# working.net
KiCad netlist of a schematic drawn in EAGLE
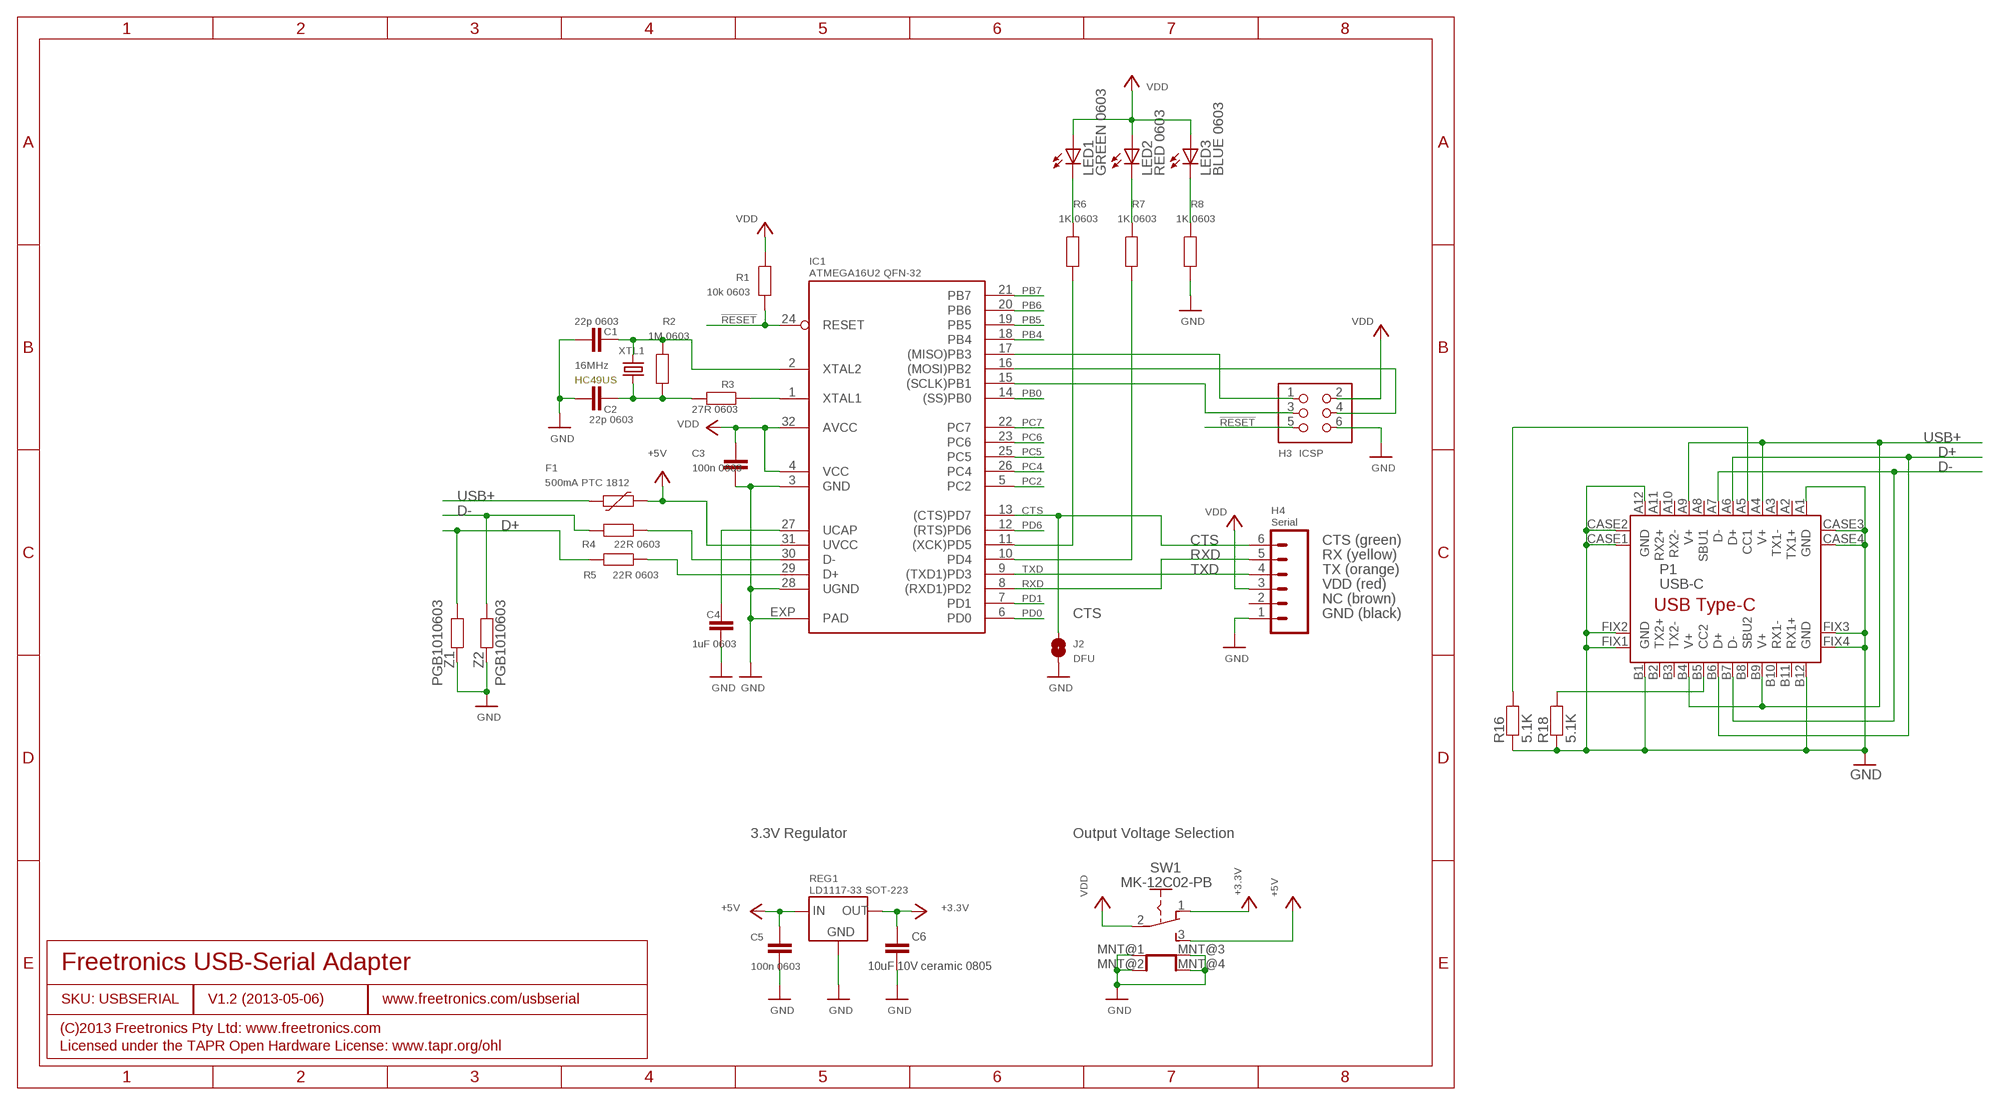
[diagram p0: schematic, sheet 1]

(export (version "E")
  (design (tool "Eeschema 10.0.6"))
  (components
    (comp (ref "C1")
      (value "22p 0603")
      (footprint "eagle-import:0603")
      (libsource (lib "eagle-import") (part "CAP0603"))
    )
    (comp (ref "C2")
      (value "22p 0603")
      (footprint "eagle-import:0603")
      (libsource (lib "eagle-import") (part "CAP0603"))
    )
    (comp (ref "C3")
      (value "100n 0603")
      (footprint "eagle-import:0603")
      (libsource (lib "eagle-import") (part "CAP0603"))
    )
    (comp (ref "C4")
      (value "1uF 0603")
      (footprint "eagle-import:0603")
      (libsource (lib "eagle-import") (part "CAP0603"))
    )
    (comp (ref "C5")
      (value "100n 0603")
      (footprint "eagle-import:0603")
      (libsource (lib "eagle-import") (part "CAP0603"))
    )
    (comp (ref "C6")
      (value "10uF 10V ceramic 0805")
      (footprint "eagle-import:C0805")
      (libsource (lib "eagle-import") (part "C-EUC0805"))
    )
    (comp (ref "F1")
      (value "500mA PTC 1812")
      (footprint "eagle-import:1812")
      (libsource (lib "eagle-import") (part "PTC"))
    )
    (comp (ref "H3")
      (value "ICSP")
      (footprint "eagle-import:HEADER_2X3")
      (libsource (lib "eagle-import") (part "HEADER_2X3"))
    )
    (comp (ref "H4")
      (value "Serial")
      (footprint "eagle-import:1X06")
      (libsource (lib "eagle-import") (part "M06SIP"))
    )
    (comp (ref "IC1")
      (value "ATMEGA16U2 QFN-32")
      (footprint "eagle-import:ATMEL_QFN32")
      (libsource (lib "eagle-import") (part "ATMEL_ATMEGA8U2-MUQFN"))
    )
    (comp (ref "J2") (value "DFU") (footprint "eagle-import:SJ") (libsource (lib "eagle-import") (part "SJ")))
    (comp (ref "LED1")
      (value "GREEN 0603")
      (footprint "eagle-import:LED-0603")
      (libsource (lib "eagle-import") (part "LED0603"))
    )
    (comp (ref "LED2")
      (value "RED 0603")
      (footprint "eagle-import:LED-0603")
      (libsource (lib "eagle-import") (part "LED0603"))
    )
    (comp (ref "LED3")
      (value "BLUE 0603")
      (footprint "eagle-import:LED-0603")
      (libsource (lib "eagle-import") (part "LED0603"))
    )
    (comp (ref "P1")
      (value "USB-C")
      (footprint "eagle-import:USB-C-U52A")
      (libsource (lib "eagle-import") (part "USB-C"))
    )
    (comp (ref "R1")
      (value "10k 0603")
      (footprint "eagle-import:0603")
      (libsource (lib "eagle-import") (part "RESISTOR0603"))
    )
    (comp (ref "R2")
      (value "1M 0603")
      (footprint "eagle-import:0603")
      (libsource (lib "eagle-import") (part "RESISTOR0603"))
    )
    (comp (ref "R3")
      (value "27R 0603")
      (footprint "eagle-import:0603")
      (libsource (lib "eagle-import") (part "RESISTOR0603"))
    )
    (comp (ref "R4")
      (value "22R 0603")
      (footprint "eagle-import:0603")
      (libsource (lib "eagle-import") (part "RESISTOR0603"))
    )
    (comp (ref "R5")
      (value "22R 0603")
      (footprint "eagle-import:0603")
      (libsource (lib "eagle-import") (part "RESISTOR0603"))
    )
    (comp (ref "R6")
      (value "1K 0603")
      (footprint "eagle-import:0603")
      (libsource (lib "eagle-import") (part "RESISTOR0603"))
    )
    (comp (ref "R7")
      (value "1K 0603")
      (footprint "eagle-import:0603")
      (libsource (lib "eagle-import") (part "RESISTOR0603"))
    )
    (comp (ref "R8")
      (value "1K 0603")
      (footprint "eagle-import:0603")
      (libsource (lib "eagle-import") (part "RESISTOR0603"))
    )
    (comp (ref "R16")
      (value "5.1K")
      (footprint "eagle-import:0603")
      (libsource (lib "eagle-import") (part "freetronics-original_RESISTOR0603"))
    )
    (comp (ref "R18")
      (value "5.1K")
      (footprint "eagle-import:0603")
      (libsource (lib "eagle-import") (part "freetronics-original_RESISTOR0603"))
    )
    (comp (ref "REG1")
      (value "LD1117-33 SOT-223")
      (footprint "eagle-import:SOT-223")
      (libsource (lib "eagle-import") (part "LD1117-FIXED"))
    )
    (comp (ref "SW1")
      (value "MK-12C02-PB")
      (footprint "eagle-import:MK-12C02")
      (libsource (lib "eagle-import") (part "SWITCH-SPDT-4TABSSMT"))
    )
    (comp (ref "XTL1")
      (value "16MHz")
      (footprint "eagle-import:HC49U-V")
      (libsource (lib "eagle-import") (part "CRYSTALHC49UV"))
    )
    (comp (ref "Z1")
      (value "PGB1010603")
      (footprint "eagle-import:0603")
      (libsource (lib "eagle-import") (part "RESISTOR0603"))
    )
    (comp (ref "Z2")
      (value "PGB1010603")
      (footprint "eagle-import:0603")
      (libsource (lib "eagle-import") (part "RESISTOR0603"))
    )
  )
  (nets
    (net (code "1") (name "+3.3V") (class "Default")
      (node (ref "C6") (pin "1") (pinfunction "1_1") (pintype "passive"))
      (node (ref "REG1") (pin "2") (pinfunction "OUT_2") (pintype "power_in"))
      (node (ref "REG1") (pin "4") (pinfunction "OUT_4") (pintype "power_in"))
      (node (ref "SW1") (pin "1") (pinfunction "A_1") (pintype "passive"))
    )
    (net (code "2") (name "+5V") (class "Default")
      (node (ref "C5") (pin "1") (pinfunction "1_1") (pintype "passive"))
      (node (ref "F1") (pin "2") (pinfunction "P$2_2") (pintype "bidirectional"))
      (node (ref "IC1") (pin "31") (pinfunction "UVCC_31") (pintype "power_in"))
      (node (ref "REG1") (pin "3") (pinfunction "IN_3") (pintype "input"))
      (node (ref "SW1") (pin "3") (pinfunction "B_3") (pintype "passive"))
    )
    (net (code "3") (name "/CTS") (class "Default")
      (node (ref "H4") (pin "6") (pinfunction "6_6") (pintype "passive"))
      (node (ref "IC1") (pin "13") (pinfunction "(CTS)PD7_13") (pintype "bidirectional"))
      (node (ref "J2") (pin "2") (pinfunction "2_2") (pintype "passive"))
    )
    (net (code "4") (name "/D+") (class "Default")
      (node (ref "P1") (pin "A6") (pinfunction "D+_A6") (pintype "bidirectional"))
      (node (ref "P1") (pin "B6") (pinfunction "D+_B6") (pintype "bidirectional"))
      (node (ref "R5") (pin "2") (pinfunction "2_2") (pintype "passive"))
      (node (ref "Z1") (pin "1") (pinfunction "1_1") (pintype "passive"))
    )
    (net (code "5") (name "/D-") (class "Default")
      (node (ref "P1") (pin "A7") (pinfunction "D-_A7") (pintype "bidirectional"))
      (node (ref "P1") (pin "B7") (pinfunction "D-_B7") (pintype "bidirectional"))
      (node (ref "R4") (pin "2") (pinfunction "2_2") (pintype "passive"))
      (node (ref "Z2") (pin "1") (pinfunction "1_1") (pintype "passive"))
    )
    (net (code "6") (name "/PB0") (class "Default")
      (node (ref "IC1") (pin "14") (pinfunction "(SS)PB0_14") (pintype "bidirectional"))
    )
    (net (code "7") (name "/PB4") (class "Default")
      (node (ref "IC1") (pin "18") (pinfunction "PB4_18") (pintype "bidirectional"))
    )
    (net (code "8") (name "/PB5") (class "Default")
      (node (ref "IC1") (pin "19") (pinfunction "PB5_19") (pintype "bidirectional"))
    )
    (net (code "9") (name "/PB6") (class "Default")
      (node (ref "IC1") (pin "20") (pinfunction "PB6_20") (pintype "bidirectional"))
    )
    (net (code "10") (name "/PB7") (class "Default")
      (node (ref "IC1") (pin "21") (pinfunction "PB7_21") (pintype "bidirectional"))
    )
    (net (code "11") (name "/PC2") (class "Default")
      (node (ref "IC1") (pin "5") (pinfunction "PC2_5") (pintype "bidirectional"))
    )
    (net (code "12") (name "/PC4") (class "Default")
      (node (ref "IC1") (pin "26") (pinfunction "PC4_26") (pintype "bidirectional"))
    )
    (net (code "13") (name "/PC5") (class "Default")
      (node (ref "IC1") (pin "25") (pinfunction "PC5_25") (pintype "bidirectional"))
    )
    (net (code "14") (name "/PC6") (class "Default")
      (node (ref "IC1") (pin "23") (pinfunction "PC6_23") (pintype "bidirectional"))
    )
    (net (code "15") (name "/PC7") (class "Default")
      (node (ref "IC1") (pin "22") (pinfunction "PC7_22") (pintype "bidirectional"))
    )
    (net (code "16") (name "/PD0") (class "Default")
      (node (ref "IC1") (pin "6") (pinfunction "PD0_6") (pintype "bidirectional"))
    )
    (net (code "17") (name "/PD1") (class "Default")
      (node (ref "IC1") (pin "7") (pinfunction "PD1_7") (pintype "bidirectional"))
    )
    (net (code "18") (name "/PD6") (class "Default")
      (node (ref "IC1") (pin "12") (pinfunction "(RTS)PD6_12") (pintype "bidirectional"))
    )
    (net (code "19") (name "/RXD") (class "Default")
      (node (ref "H4") (pin "5") (pinfunction "5_5") (pintype "passive"))
      (node (ref "IC1") (pin "8") (pinfunction "(RXD1)PD2_8") (pintype "bidirectional"))
    )
    (net (code "20") (name "/TXD") (class "Default")
      (node (ref "H4") (pin "4") (pinfunction "4_4") (pintype "passive"))
      (node (ref "IC1") (pin "9") (pinfunction "(TXD1)PD3_9") (pintype "bidirectional"))
    )
    (net (code "21") (name "/USB+") (class "Default")
      (node (ref "F1") (pin "1") (pinfunction "P$1_1") (pintype "bidirectional"))
      (node (ref "P1") (pin "A4") (pinfunction "V+_A4") (pintype "power_in"))
      (node (ref "P1") (pin "A9") (pinfunction "V+_A9") (pintype "power_in"))
      (node (ref "P1") (pin "B4") (pinfunction "V+_B4") (pintype "power_in"))
      (node (ref "P1") (pin "B9") (pinfunction "V+_B9") (pintype "power_in"))
    )
    (net (code "22") (name "/~{RESET}") (class "Default")
      (node (ref "H3") (pin "5") (pinfunction "5_5") (pintype "passive"))
      (node (ref "IC1") (pin "24") (pinfunction "RESET_24") (pintype "input"))
      (node (ref "R1") (pin "1") (pinfunction "1_1") (pintype "passive"))
    )
    (net (code "23") (name "GND") (class "Default")
      (node (ref "C1") (pin "1") (pinfunction "1_1") (pintype "passive"))
      (node (ref "C2") (pin "1") (pinfunction "1_1") (pintype "passive"))
      (node (ref "C3") (pin "2") (pinfunction "2_2") (pintype "passive"))
      (node (ref "C4") (pin "2") (pinfunction "2_2") (pintype "passive"))
      (node (ref "C5") (pin "2") (pinfunction "2_2") (pintype "passive"))
      (node (ref "C6") (pin "2") (pinfunction "2_2") (pintype "passive"))
      (node (ref "H3") (pin "6") (pinfunction "6_6") (pintype "passive"))
      (node (ref "H4") (pin "1") (pinfunction "1_1") (pintype "passive"))
      (node (ref "IC1") (pin "28") (pinfunction "UGND_28") (pintype "power_in"))
      (node (ref "IC1") (pin "3") (pinfunction "GND_3") (pintype "power_in"))
      (node (ref "IC1") (pin "EXP") (pinfunction "PAD_EXP") (pintype "power_in"))
      (node (ref "J2") (pin "1") (pinfunction "1_1") (pintype "passive"))
      (node (ref "P1") (pin "A1") (pinfunction "GND_A1") (pintype "power_in"))
      (node (ref "P1") (pin "A12") (pinfunction "GND_A12") (pintype "power_in"))
      (node (ref "P1") (pin "B1") (pinfunction "GND_B1") (pintype "power_in"))
      (node (ref "P1") (pin "B12") (pinfunction "GND_B12") (pintype "power_in"))
      (node (ref "P1") (pin "CASE1") (pinfunction "GND_CASE1") (pintype "power_in"))
      (node (ref "P1") (pin "CASE2") (pinfunction "GND_CASE2") (pintype "power_in"))
      (node (ref "P1") (pin "CASE3") (pinfunction "GND_CASE3") (pintype "power_in"))
      (node (ref "P1") (pin "CASE4") (pinfunction "GND_CASE4") (pintype "power_in"))
      (node (ref "P1") (pin "FIX1") (pinfunction "GND_FIX1") (pintype "power_in"))
      (node (ref "P1") (pin "FIX2") (pinfunction "GND_FIX2") (pintype "power_in"))
      (node (ref "P1") (pin "FIX3") (pinfunction "GND_FIX3") (pintype "power_in"))
      (node (ref "P1") (pin "FIX4") (pinfunction "GND_FIX4") (pintype "power_in"))
      (node (ref "R16") (pin "1") (pinfunction "1_1") (pintype "passive"))
      (node (ref "R18") (pin "1") (pinfunction "1_1") (pintype "passive"))
      (node (ref "R8") (pin "1") (pinfunction "1_1") (pintype "passive"))
      (node (ref "REG1") (pin "1") (pinfunction "GND_1") (pintype "input"))
      (node (ref "SW1") (pin "MNT@1") (pinfunction "MNT_MNT@1") (pintype "bidirectional"))
      (node (ref "SW1") (pin "MNT@2") (pinfunction "MNT_MNT@2") (pintype "bidirectional"))
      (node (ref "SW1") (pin "MNT@3") (pinfunction "MNT_MNT@3") (pintype "bidirectional"))
      (node (ref "SW1") (pin "MNT@4") (pinfunction "MNT_MNT@4") (pintype "bidirectional"))
      (node (ref "Z1") (pin "2") (pinfunction "2_2") (pintype "passive"))
      (node (ref "Z2") (pin "2") (pinfunction "2_2") (pintype "passive"))
    )
    (net (code "24") (name "Net-(C2-Pad2)") (class "Default")
      (node (ref "C2") (pin "2") (pinfunction "2_2") (pintype "passive"))
      (node (ref "R2") (pin "1") (pinfunction "1_1") (pintype "passive"))
      (node (ref "R3") (pin "2") (pinfunction "2_2") (pintype "passive"))
      (node (ref "XTL1") (pin "1") (pinfunction "1_1") (pintype "passive"))
    )
    (net (code "25") (name "Net-(IC1-(MISO)PB3)") (class "Default")
      (node (ref "H3") (pin "1") (pinfunction "1_1") (pintype "passive"))
      (node (ref "IC1") (pin "17") (pinfunction "(MISO)PB3_17") (pintype "bidirectional"))
    )
    (net (code "26") (name "Net-(IC1-(MOSI)PB2)") (class "Default")
      (node (ref "H3") (pin "4") (pinfunction "4_4") (pintype "passive"))
      (node (ref "IC1") (pin "16") (pinfunction "(MOSI)PB2_16") (pintype "bidirectional"))
    )
    (net (code "27") (name "Net-(IC1-(SCLK)PB1)") (class "Default")
      (node (ref "H3") (pin "3") (pinfunction "3_3") (pintype "passive"))
      (node (ref "IC1") (pin "15") (pinfunction "(SCLK)PB1_15") (pintype "bidirectional"))
    )
    (net (code "28") (name "Net-(IC1-(XCK)PD5)") (class "Default")
      (node (ref "IC1") (pin "11") (pinfunction "(XCK)PD5_11") (pintype "bidirectional"))
      (node (ref "R6") (pin "1") (pinfunction "1_1") (pintype "passive"))
    )
    (net (code "29") (name "Net-(IC1-D+)") (class "Default")
      (node (ref "IC1") (pin "29") (pinfunction "D+_29") (pintype "bidirectional"))
      (node (ref "R5") (pin "1") (pinfunction "1_1") (pintype "passive"))
    )
    (net (code "30") (name "Net-(IC1-D-)") (class "Default")
      (node (ref "IC1") (pin "30") (pinfunction "D-_30") (pintype "bidirectional"))
      (node (ref "R4") (pin "1") (pinfunction "1_1") (pintype "passive"))
    )
    (net (code "31") (name "Net-(IC1-PD4)") (class "Default")
      (node (ref "IC1") (pin "10") (pinfunction "PD4_10") (pintype "bidirectional"))
      (node (ref "R7") (pin "1") (pinfunction "1_1") (pintype "passive"))
    )
    (net (code "32") (name "Net-(IC1-UCAP)") (class "Default")
      (node (ref "C4") (pin "1") (pinfunction "1_1") (pintype "passive"))
      (node (ref "IC1") (pin "27") (pinfunction "UCAP_27") (pintype "passive"))
    )
    (net (code "33") (name "Net-(IC1-XTAL1)") (class "Default")
      (node (ref "IC1") (pin "1") (pinfunction "XTAL1_1") (pintype "bidirectional"))
      (node (ref "R3") (pin "1") (pinfunction "1_1") (pintype "passive"))
    )
    (net (code "34") (name "Net-(IC1-XTAL2)") (class "Default")
      (node (ref "C1") (pin "2") (pinfunction "2_2") (pintype "passive"))
      (node (ref "IC1") (pin "2") (pinfunction "XTAL2_2") (pintype "bidirectional"))
      (node (ref "R2") (pin "2") (pinfunction "2_2") (pintype "passive"))
      (node (ref "XTL1") (pin "2") (pinfunction "2_2") (pintype "passive"))
    )
    (net (code "35") (name "Net-(LED1-PadC)") (class "Default")
      (node (ref "LED1") (pin "C") (pinfunction "C_C") (pintype "passive"))
      (node (ref "R6") (pin "2") (pinfunction "2_2") (pintype "passive"))
    )
    (net (code "36") (name "Net-(LED2-PadC)") (class "Default")
      (node (ref "LED2") (pin "C") (pinfunction "C_C") (pintype "passive"))
      (node (ref "R7") (pin "2") (pinfunction "2_2") (pintype "passive"))
    )
    (net (code "37") (name "Net-(LED3-PadC)") (class "Default")
      (node (ref "LED3") (pin "C") (pinfunction "C_C") (pintype "passive"))
      (node (ref "R8") (pin "2") (pinfunction "2_2") (pintype "passive"))
    )
    (net (code "38") (name "Net-(P1-CC1)") (class "Default")
      (node (ref "P1") (pin "A5") (pinfunction "CC1_A5") (pintype "bidirectional"))
      (node (ref "R16") (pin "2") (pinfunction "2_2") (pintype "passive"))
    )
    (net (code "39") (name "Net-(P1-CC2)") (class "Default")
      (node (ref "P1") (pin "B5") (pinfunction "CC2_B5") (pintype "bidirectional"))
      (node (ref "R18") (pin "2") (pinfunction "2_2") (pintype "passive"))
    )
    (net (code "40") (name "VDD") (class "Default")
      (node (ref "C3") (pin "1") (pinfunction "1_1") (pintype "passive"))
      (node (ref "H3") (pin "2") (pinfunction "2_2") (pintype "passive"))
      (node (ref "H4") (pin "3") (pinfunction "3_3") (pintype "passive"))
      (node (ref "IC1") (pin "32") (pinfunction "AVCC_32") (pintype "power_in"))
      (node (ref "IC1") (pin "4") (pinfunction "VCC_4") (pintype "power_in"))
      (node (ref "LED1") (pin "A") (pinfunction "A_A") (pintype "passive"))
      (node (ref "LED2") (pin "A") (pinfunction "A_A") (pintype "passive"))
      (node (ref "LED3") (pin "A") (pinfunction "A_A") (pintype "passive"))
      (node (ref "R1") (pin "2") (pinfunction "2_2") (pintype "passive"))
      (node (ref "SW1") (pin "2") (pinfunction "COM_2") (pintype "passive"))
    )
    (net (code "41") (name "unconnected-(H4-Pad2)") (class "Default")
      (node (ref "H4") (pin "2") (pinfunction "2_2") (pintype "passive"))
    )
    (net (code "42") (name "unconnected-(P1-RX1+-PadB11)") (class "Default")
      (node (ref "P1") (pin "B11") (pinfunction "RX1+_B11") (pintype "bidirectional"))
    )
    (net (code "43") (name "unconnected-(P1-RX1--PadB10)") (class "Default")
      (node (ref "P1") (pin "B10") (pinfunction "RX1-_B10") (pintype "bidirectional"))
    )
    (net (code "44") (name "unconnected-(P1-RX2+-PadA11)") (class "Default")
      (node (ref "P1") (pin "A11") (pinfunction "RX2+_A11") (pintype "bidirectional"))
    )
    (net (code "45") (name "unconnected-(P1-RX2--PadA10)") (class "Default")
      (node (ref "P1") (pin "A10") (pinfunction "RX2-_A10") (pintype "bidirectional"))
    )
    (net (code "46") (name "unconnected-(P1-SBU1-PadA8)") (class "Default")
      (node (ref "P1") (pin "A8") (pinfunction "SBU1_A8") (pintype "bidirectional"))
    )
    (net (code "47") (name "unconnected-(P1-SBU2-PadB8)") (class "Default")
      (node (ref "P1") (pin "B8") (pinfunction "SBU2_B8") (pintype "bidirectional"))
    )
    (net (code "48") (name "unconnected-(P1-TX1+-PadA2)") (class "Default")
      (node (ref "P1") (pin "A2") (pinfunction "TX1+_A2") (pintype "bidirectional"))
    )
    (net (code "49") (name "unconnected-(P1-TX1--PadA3)") (class "Default")
      (node (ref "P1") (pin "A3") (pinfunction "TX1-_A3") (pintype "bidirectional"))
    )
    (net (code "50") (name "unconnected-(P1-TX2+-PadB2)") (class "Default")
      (node (ref "P1") (pin "B2") (pinfunction "TX2+_B2") (pintype "bidirectional"))
    )
    (net (code "51") (name "unconnected-(P1-TX2--PadB3)") (class "Default")
      (node (ref "P1") (pin "B3") (pinfunction "TX2-_B3") (pintype "bidirectional"))
    )
  )
)
